# Connectors.net
KiCad netlist of a schematic drawn in Altium Designer
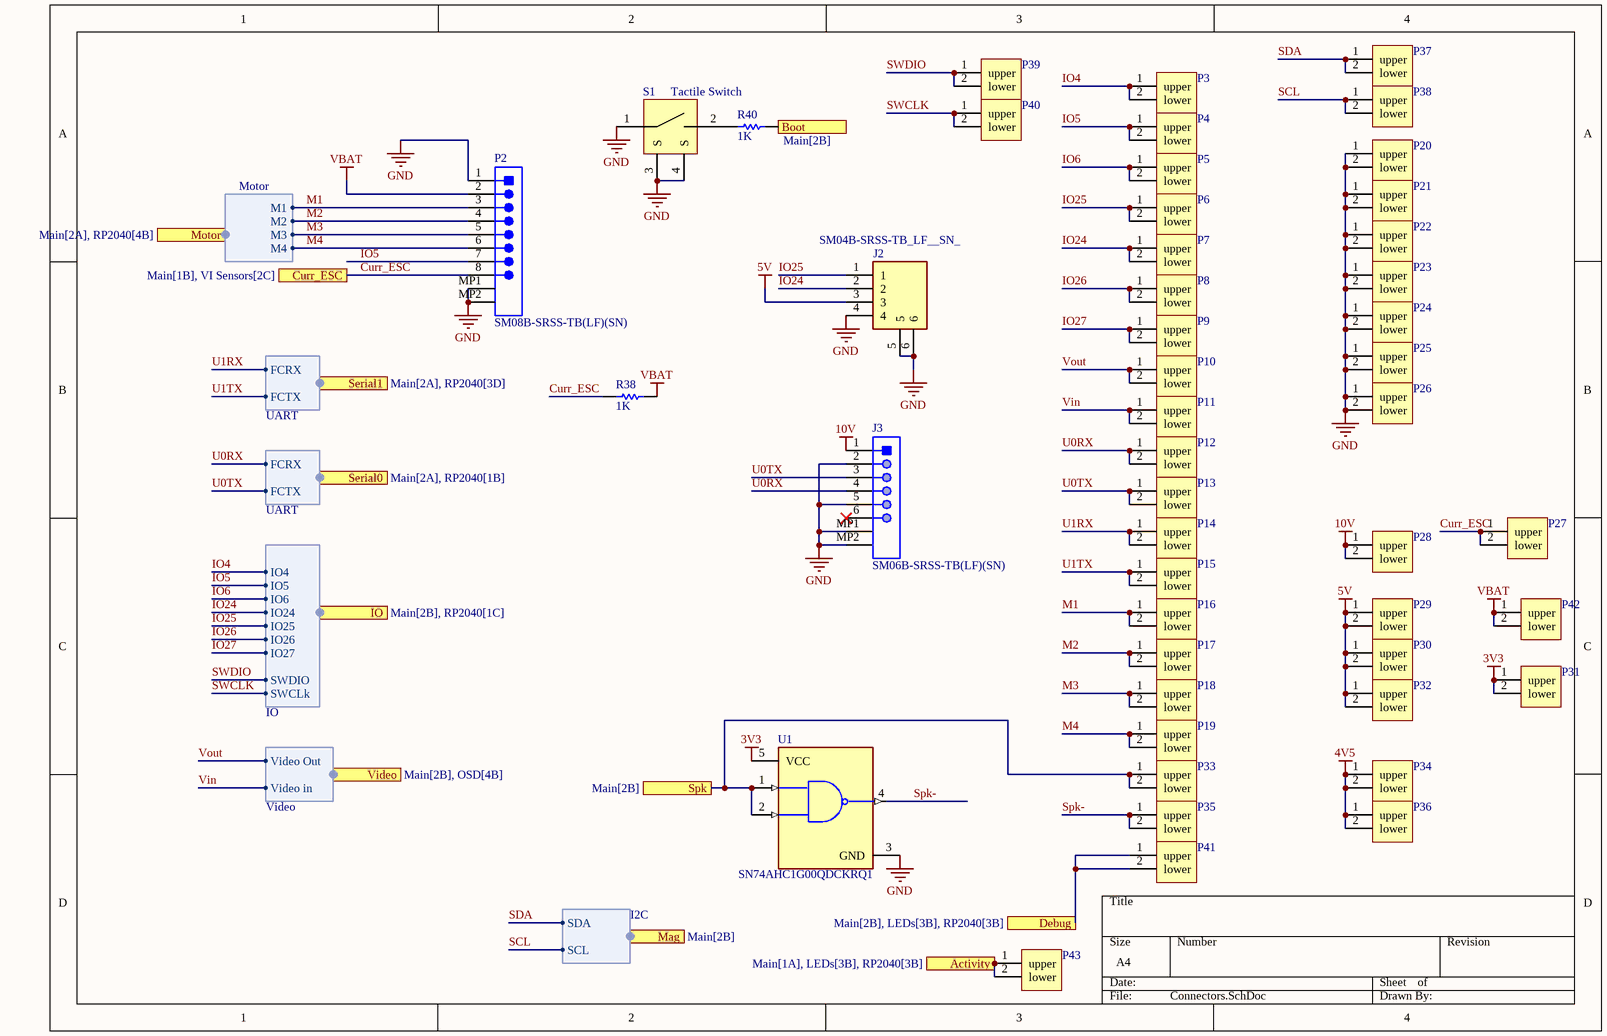
[diagram p0: Connectors.SchDoc]

(export (version "E")
  (design (tool "Eeschema 10.0.6"))
  (components
    (comp (ref "J2")
      (value "SM04B-SRSS-TB_LF__SN_")
      (footprint "SM04B-SRSS-TB(LFSN)")
      (description "Connector")
      (fields (field (name "MANUFACTURER_PART_NUMBER") "SM04B-SRSS-TB(LF)(SN)"))
      (libsource (lib "Custom Components") (part "SM04B-SRSS-TB_LF__SN_"))
    )
    (comp (ref "J3")
      (value "SM06B-SRSS-TB(LF)(SN)")
      (footprint "JST-SM06B-SRSS-TB_V")
      (description "Male Header, Pitch 1 mm, 1 x 6 Position, Height 2.95 mm, -25 to 85 degC, RoHS, Tape and Reel")
      (fields (field (name "MANUFACTURER") "JST"))
      (libsource (lib "Altium Content Vault") (part "CN-1P-2M-R6"))
    )
    (comp (ref "P2")
      (value "SM08B-SRSS-TB(LF)(SN)")
      (footprint "JST-SM08B-SRSS-TB_V")
      (description "Male Header, Pitch 1 mm, 1 x 8 Position, Height 2.95 mm, -25 to 85 degC, RoHS, Tape and Reel")
      (fields (field (name "MANUFACTURER") "JST"))
      (libsource (lib "Altium Content Vault") (part "CN-1P-2M-R8"))
    )
    (comp (ref "P3")
      (value "solder pad rounded double sided")
      (footprint "solder pad double sided rounded - duplicate")
      (libsource (lib "Custom Components") (part "solder pad rounded double sided"))
    )
    (comp (ref "P4")
      (value "solder pad rounded double sided")
      (footprint "solder pad double sided rounded - duplicate")
      (libsource (lib "Custom Components") (part "solder pad rounded double sided"))
    )
    (comp (ref "P5")
      (value "solder pad rounded double sided")
      (footprint "solder pad double sided rounded - duplicate")
      (libsource (lib "Custom Components") (part "solder pad rounded double sided"))
    )
    (comp (ref "P6")
      (value "solder pad rounded double sided")
      (footprint "solder pad double sided rounded - duplicate")
      (libsource (lib "Custom Components") (part "solder pad rounded double sided"))
    )
    (comp (ref "P7")
      (value "solder pad rounded double sided")
      (footprint "solder pad double sided rounded - duplicate")
      (libsource (lib "Custom Components") (part "solder pad rounded double sided"))
    )
    (comp (ref "P8")
      (value "solder pad rounded double sided")
      (footprint "solder pad double sided rounded - duplicate")
      (libsource (lib "Custom Components") (part "solder pad rounded double sided"))
    )
    (comp (ref "P9")
      (value "solder pad rounded double sided")
      (footprint "solder pad double sided rounded - duplicate")
      (libsource (lib "Custom Components") (part "solder pad rounded double sided"))
    )
    (comp (ref "P10")
      (value "solder pad rounded double sided")
      (footprint "solder pad double sided rounded - duplicate")
      (libsource (lib "Custom Components") (part "solder pad rounded double sided"))
    )
    (comp (ref "P11")
      (value "solder pad rounded double sided")
      (footprint "solder pad double sided rounded - duplicate")
      (libsource (lib "Custom Components") (part "solder pad rounded double sided"))
    )
    (comp (ref "P12")
      (value "solder pad rounded double sided")
      (footprint "solder pad double sided rounded - duplicate")
      (libsource (lib "Custom Components") (part "solder pad rounded double sided"))
    )
    (comp (ref "P13")
      (value "solder pad rounded double sided")
      (footprint "solder pad double sided rounded - duplicate")
      (libsource (lib "Custom Components") (part "solder pad rounded double sided"))
    )
    (comp (ref "P14")
      (value "solder pad rounded double sided")
      (footprint "solder pad double sided rounded - duplicate")
      (libsource (lib "Custom Components") (part "solder pad rounded double sided"))
    )
    (comp (ref "P15")
      (value "solder pad rounded double sided")
      (footprint "solder pad double sided rounded - duplicate")
      (libsource (lib "Custom Components") (part "solder pad rounded double sided"))
    )
    (comp (ref "P16")
      (value "solder pad rounded double sided")
      (footprint "solder pad double sided rounded - duplicate")
      (libsource (lib "Custom Components") (part "solder pad rounded double sided"))
    )
    (comp (ref "P17")
      (value "solder pad rounded double sided")
      (footprint "solder pad double sided rounded - duplicate")
      (libsource (lib "Custom Components") (part "solder pad rounded double sided"))
    )
    (comp (ref "P18")
      (value "solder pad rounded double sided")
      (footprint "solder pad double sided rounded - duplicate")
      (libsource (lib "Custom Components") (part "solder pad rounded double sided"))
    )
    (comp (ref "P19")
      (value "solder pad rounded double sided")
      (footprint "solder pad double sided rounded - duplicate")
      (libsource (lib "Custom Components") (part "solder pad rounded double sided"))
    )
    (comp (ref "P20")
      (value "solder pad square double sided")
      (footprint "solder pad double sided square")
      (libsource (lib "Custom Components") (part "solder pad square double sided"))
    )
    (comp (ref "P21")
      (value "solder pad square double sided")
      (footprint "solder pad double sided square")
      (libsource (lib "Custom Components") (part "solder pad square double sided"))
    )
    (comp (ref "P22")
      (value "solder pad square double sided")
      (footprint "solder pad double sided square")
      (libsource (lib "Custom Components") (part "solder pad square double sided"))
    )
    (comp (ref "P23")
      (value "solder pad square double sided")
      (footprint "solder pad double sided square")
      (libsource (lib "Custom Components") (part "solder pad square double sided"))
    )
    (comp (ref "P24")
      (value "solder pad square double sided")
      (footprint "solder pad double sided square")
      (libsource (lib "Custom Components") (part "solder pad square double sided"))
    )
    (comp (ref "P25")
      (value "solder pad square double sided")
      (footprint "solder pad double sided square")
      (libsource (lib "Custom Components") (part "solder pad square double sided"))
    )
    (comp (ref "P26")
      (value "solder pad square double sided")
      (footprint "solder pad double sided square")
      (libsource (lib "Custom Components") (part "solder pad square double sided"))
    )
    (comp (ref "P27")
      (value "solder pad rounded double sided")
      (footprint "solder pad double sided rounded - duplicate")
      (libsource (lib "Custom Components") (part "solder pad rounded double sided"))
    )
    (comp (ref "P28")
      (value "solder pad chamfered double sided")
      (footprint "solder pad double sided chamfered")
      (libsource (lib "Custom Components") (part "solder pad chamfered double sided"))
    )
    (comp (ref "P29")
      (value "solder pad chamfered double sided")
      (footprint "solder pad double sided chamfered")
      (libsource (lib "Custom Components") (part "solder pad chamfered double sided"))
    )
    (comp (ref "P30")
      (value "solder pad chamfered double sided")
      (footprint "solder pad double sided chamfered")
      (libsource (lib "Custom Components") (part "solder pad chamfered double sided"))
    )
    (comp (ref "P31")
      (value "solder pad chamfered double sided")
      (footprint "solder pad double sided chamfered")
      (libsource (lib "Custom Components") (part "solder pad chamfered double sided"))
    )
    (comp (ref "P32")
      (value "solder pad chamfered double sided")
      (footprint "solder pad double sided chamfered")
      (libsource (lib "Custom Components") (part "solder pad chamfered double sided"))
    )
    (comp (ref "P33")
      (value "solder pad rounded double sided")
      (footprint "solder pad double sided rounded - duplicate")
      (libsource (lib "Custom Components") (part "solder pad rounded double sided"))
    )
    (comp (ref "P34")
      (value "solder pad chamfered double sided")
      (footprint "solder pad double sided chamfered")
      (libsource (lib "Custom Components") (part "solder pad chamfered double sided"))
    )
    (comp (ref "P35")
      (value "solder pad rounded double sided")
      (footprint "solder pad double sided rounded - duplicate")
      (libsource (lib "Custom Components") (part "solder pad rounded double sided"))
    )
    (comp (ref "P36")
      (value "solder pad chamfered double sided")
      (footprint "solder pad double sided chamfered")
      (libsource (lib "Custom Components") (part "solder pad chamfered double sided"))
    )
    (comp (ref "P37")
      (value "solder pad rounded double sided")
      (footprint "solder pad double sided rounded - duplicate")
      (libsource (lib "Custom Components") (part "solder pad rounded double sided"))
    )
    (comp (ref "P38")
      (value "solder pad rounded double sided")
      (footprint "solder pad double sided rounded - duplicate")
      (libsource (lib "Custom Components") (part "solder pad rounded double sided"))
    )
    (comp (ref "P39")
      (value "solder pad rounded double sided")
      (footprint "solder pad double sided rounded - duplicate")
      (libsource (lib "Custom Components") (part "solder pad rounded double sided"))
    )
    (comp (ref "P40")
      (value "solder pad rounded double sided")
      (footprint "solder pad double sided rounded - duplicate")
      (libsource (lib "Custom Components") (part "solder pad rounded double sided"))
    )
    (comp (ref "P41")
      (value "solder pad rounded double sided")
      (footprint "solder pad double sided rounded - duplicate")
      (libsource (lib "Custom Components") (part "solder pad rounded double sided"))
    )
    (comp (ref "P42")
      (value "solder pad chamfered double sided")
      (footprint "solder pad double sided chamfered")
      (libsource (lib "Custom Components") (part "solder pad chamfered double sided"))
    )
    (comp (ref "P43")
      (value "solder pad rounded double sided")
      (footprint "solder pad double sided rounded - duplicate")
      (libsource (lib "Custom Components") (part "solder pad rounded double sided"))
    )
    (comp (ref "R38")
      (value "1K")
      (footprint "RESC0603(1608)_N")
      (description "Chipwiderstand, SMD, Baureihe MC, 1%")
      (fields (field (name "MANUFACTURER") "Multicomp"))
      (libsource (lib "Standardbauteile") (part "Res 1K"))
    )
    (comp (ref "R40")
      (value "1K")
      (footprint "RESC1005X40X25NL05T10")
      (fields (field (name "MANUFACTURER") "Yageo / Phycomp") (field (name "PART NUMBER") "RC0402JR-070RL"))
      (libsource (lib "Altium Content Vault") (part "RES"))
    )
    (comp (ref "S1")
      (value "Tactile Switch")
      (footprint "Tactile Switch")
      (libsource (lib "Custom Components") (part "Tactile Switch"))
    )
    (comp (ref "U1")
      (value "SN74AHC1G00QDCKRQ1")
      (footprint "FP-DCK0005A-IPC_A")
      (description "IC GATE NAND 1CH 2-INP SC70-5")
      (libsource (lib "Altium Content Vault") (part "4a1d673274a90161e31fa41c5f74738"))
    )
  )
  (nets
    (net (code "6") (name "/Activity") (class "Default")
      (node (ref "P43") (pin "1") (pinfunction "upper_1") (pintype "passive"))
      (node (ref "P43") (pin "2") (pinfunction "lower_2") (pintype "passive"))
    )
    (net (code "7") (name "/Boot") (class "Default")
      (node (ref "R40") (pin "2") (pinfunction "2_2") (pintype "passive"))
    )
    (net (code "8") (name "/Curr_ESC") (class "Default")
      (node (ref "P2") (pin "8") (pinfunction "8_8") (pintype "passive"))
      (node (ref "P27") (pin "1") (pinfunction "upper_1") (pintype "passive"))
      (node (ref "P27") (pin "2") (pinfunction "lower_2") (pintype "passive"))
      (node (ref "R38") (pin "1") (pinfunction "1_1") (pintype "passive"))
    )
    (net (code "9") (name "/Debug") (class "Default")
      (node (ref "P41") (pin "1") (pinfunction "upper_1") (pintype "passive"))
      (node (ref "P41") (pin "2") (pinfunction "lower_2") (pintype "passive"))
    )
    (net (code "10") (name "/IO4") (class "Default")
      (node (ref "P3") (pin "1") (pinfunction "upper_1") (pintype "passive"))
      (node (ref "P3") (pin "2") (pinfunction "lower_2") (pintype "passive"))
    )
    (net (code "11") (name "/IO5") (class "Default")
      (node (ref "P2") (pin "7") (pinfunction "7_7") (pintype "passive"))
      (node (ref "P4") (pin "1") (pinfunction "upper_1") (pintype "passive"))
      (node (ref "P4") (pin "2") (pinfunction "lower_2") (pintype "passive"))
    )
    (net (code "12") (name "/IO6") (class "Default")
      (node (ref "P5") (pin "1") (pinfunction "upper_1") (pintype "passive"))
      (node (ref "P5") (pin "2") (pinfunction "lower_2") (pintype "passive"))
    )
    (net (code "13") (name "/IO24") (class "Default")
      (node (ref "J2") (pin "2") (pinfunction "2_2") (pintype "passive"))
      (node (ref "P7") (pin "1") (pinfunction "upper_1") (pintype "passive"))
      (node (ref "P7") (pin "2") (pinfunction "lower_2") (pintype "passive"))
    )
    (net (code "14") (name "/IO25") (class "Default")
      (node (ref "J2") (pin "1") (pinfunction "1_1") (pintype "passive"))
      (node (ref "P6") (pin "1") (pinfunction "upper_1") (pintype "passive"))
      (node (ref "P6") (pin "2") (pinfunction "lower_2") (pintype "passive"))
    )
    (net (code "15") (name "/IO26") (class "Default")
      (node (ref "P8") (pin "1") (pinfunction "upper_1") (pintype "passive"))
      (node (ref "P8") (pin "2") (pinfunction "lower_2") (pintype "passive"))
    )
    (net (code "16") (name "/IO27") (class "Default")
      (node (ref "P9") (pin "1") (pinfunction "upper_1") (pintype "passive"))
      (node (ref "P9") (pin "2") (pinfunction "lower_2") (pintype "passive"))
    )
    (net (code "17") (name "/M1") (class "Default")
      (node (ref "P16") (pin "1") (pinfunction "upper_1") (pintype "passive"))
      (node (ref "P16") (pin "2") (pinfunction "lower_2") (pintype "passive"))
      (node (ref "P2") (pin "3") (pinfunction "3_3") (pintype "passive"))
    )
    (net (code "18") (name "/M2") (class "Default")
      (node (ref "P17") (pin "1") (pinfunction "upper_1") (pintype "passive"))
      (node (ref "P17") (pin "2") (pinfunction "lower_2") (pintype "passive"))
      (node (ref "P2") (pin "4") (pinfunction "4_4") (pintype "passive"))
    )
    (net (code "19") (name "/M3") (class "Default")
      (node (ref "P18") (pin "1") (pinfunction "upper_1") (pintype "passive"))
      (node (ref "P18") (pin "2") (pinfunction "lower_2") (pintype "passive"))
      (node (ref "P2") (pin "5") (pinfunction "5_5") (pintype "passive"))
    )
    (net (code "20") (name "/M4") (class "Default")
      (node (ref "P19") (pin "1") (pinfunction "upper_1") (pintype "passive"))
      (node (ref "P19") (pin "2") (pinfunction "lower_2") (pintype "passive"))
      (node (ref "P2") (pin "6") (pinfunction "6_6") (pintype "passive"))
    )
    (net (code "21") (name "/SCL") (class "Default")
      (node (ref "P38") (pin "1") (pinfunction "upper_1") (pintype "passive"))
      (node (ref "P38") (pin "2") (pinfunction "lower_2") (pintype "passive"))
    )
    (net (code "22") (name "/SDA") (class "Default")
      (node (ref "P37") (pin "1") (pinfunction "upper_1") (pintype "passive"))
      (node (ref "P37") (pin "2") (pinfunction "lower_2") (pintype "passive"))
    )
    (net (code "23") (name "/SWCLK") (class "Default")
      (node (ref "P40") (pin "1") (pinfunction "upper_1") (pintype "passive"))
      (node (ref "P40") (pin "2") (pinfunction "lower_2") (pintype "passive"))
    )
    (net (code "24") (name "/SWDIO") (class "Default")
      (node (ref "P39") (pin "1") (pinfunction "upper_1") (pintype "passive"))
      (node (ref "P39") (pin "2") (pinfunction "lower_2") (pintype "passive"))
    )
    (net (code "25") (name "/Spk") (class "Default")
      (node (ref "P33") (pin "1") (pinfunction "upper_1") (pintype "passive"))
      (node (ref "P33") (pin "2") (pinfunction "lower_2") (pintype "passive"))
      (node (ref "U1") (pin "1") (pinfunction "A_1") (pintype "input"))
      (node (ref "U1") (pin "2") (pinfunction "B_2") (pintype "input"))
    )
    (net (code "26") (name "/Spk-") (class "Default")
      (node (ref "P35") (pin "1") (pinfunction "upper_1") (pintype "passive"))
      (node (ref "P35") (pin "2") (pinfunction "lower_2") (pintype "passive"))
      (node (ref "U1") (pin "4") (pinfunction "Y_4") (pintype "output"))
    )
    (net (code "27") (name "/U0RX") (class "Default")
      (node (ref "J3") (pin "4") (pinfunction "4_4") (pintype "passive"))
      (node (ref "P12") (pin "1") (pinfunction "upper_1") (pintype "passive"))
      (node (ref "P12") (pin "2") (pinfunction "lower_2") (pintype "passive"))
    )
    (net (code "28") (name "/U0TX") (class "Default")
      (node (ref "J3") (pin "3") (pinfunction "3_3") (pintype "passive"))
      (node (ref "P13") (pin "1") (pinfunction "upper_1") (pintype "passive"))
      (node (ref "P13") (pin "2") (pinfunction "lower_2") (pintype "passive"))
    )
    (net (code "29") (name "/U1RX") (class "Default")
      (node (ref "P14") (pin "1") (pinfunction "upper_1") (pintype "passive"))
      (node (ref "P14") (pin "2") (pinfunction "lower_2") (pintype "passive"))
    )
    (net (code "30") (name "/U1TX") (class "Default")
      (node (ref "P15") (pin "1") (pinfunction "upper_1") (pintype "passive"))
      (node (ref "P15") (pin "2") (pinfunction "lower_2") (pintype "passive"))
    )
    (net (code "31") (name "/Vin") (class "Default")
      (node (ref "P11") (pin "1") (pinfunction "upper_1") (pintype "passive"))
      (node (ref "P11") (pin "2") (pinfunction "lower_2") (pintype "passive"))
    )
    (net (code "32") (name "/Vout") (class "Default")
      (node (ref "P10") (pin "1") (pinfunction "upper_1") (pintype "passive"))
      (node (ref "P10") (pin "2") (pinfunction "lower_2") (pintype "passive"))
    )
    (net (code "38") (name "3V3") (class "Default")
      (node (ref "P31") (pin "1") (pinfunction "upper_1") (pintype "passive"))
      (node (ref "P31") (pin "2") (pinfunction "lower_2") (pintype "passive"))
      (node (ref "U1") (pin "5") (pinfunction "VCC_5") (pintype "power_in"))
    )
    (net (code "39") (name "4V5") (class "Default")
      (node (ref "P34") (pin "1") (pinfunction "upper_1") (pintype "passive"))
      (node (ref "P34") (pin "2") (pinfunction "lower_2") (pintype "passive"))
      (node (ref "P36") (pin "1") (pinfunction "upper_1") (pintype "passive"))
      (node (ref "P36") (pin "2") (pinfunction "lower_2") (pintype "passive"))
    )
    (net (code "40") (name "5V") (class "Default")
      (node (ref "J2") (pin "3") (pinfunction "3_3") (pintype "passive"))
      (node (ref "P29") (pin "1") (pinfunction "upper_1") (pintype "passive"))
      (node (ref "P29") (pin "2") (pinfunction "lower_2") (pintype "passive"))
      (node (ref "P30") (pin "1") (pinfunction "upper_1") (pintype "passive"))
      (node (ref "P30") (pin "2") (pinfunction "lower_2") (pintype "passive"))
      (node (ref "P32") (pin "1") (pinfunction "upper_1") (pintype "passive"))
      (node (ref "P32") (pin "2") (pinfunction "lower_2") (pintype "passive"))
    )
    (net (code "41") (name "10V") (class "Default")
      (node (ref "J3") (pin "1") (pinfunction "1_1") (pintype "passive"))
      (node (ref "P28") (pin "1") (pinfunction "upper_1") (pintype "passive"))
      (node (ref "P28") (pin "2") (pinfunction "lower_2") (pintype "passive"))
    )
    (net (code "42") (name "GND") (class "Default")
      (node (ref "J2") (pin "4") (pinfunction "4_4") (pintype "passive"))
      (node (ref "J2") (pin "5") (pinfunction "5_5") (pintype "passive"))
      (node (ref "J2") (pin "6") (pinfunction "6_6") (pintype "passive"))
      (node (ref "J3") (pin "2") (pinfunction "2_2") (pintype "passive"))
      (node (ref "J3") (pin "5") (pinfunction "5_5") (pintype "passive"))
      (node (ref "J3") (pin "MP1") (pinfunction "MP1_MP1") (pintype "passive"))
      (node (ref "J3") (pin "MP2") (pinfunction "MP2_MP2") (pintype "passive"))
      (node (ref "P2") (pin "1") (pinfunction "1_1") (pintype "passive"))
      (node (ref "P2") (pin "MP1") (pinfunction "MP1_MP1") (pintype "passive"))
      (node (ref "P2") (pin "MP2") (pinfunction "MP2_MP2") (pintype "passive"))
      (node (ref "P20") (pin "1") (pinfunction "upper_1") (pintype "passive"))
      (node (ref "P20") (pin "2") (pinfunction "lower_2") (pintype "passive"))
      (node (ref "P21") (pin "1") (pinfunction "upper_1") (pintype "passive"))
      (node (ref "P21") (pin "2") (pinfunction "lower_2") (pintype "passive"))
      (node (ref "P22") (pin "1") (pinfunction "upper_1") (pintype "passive"))
      (node (ref "P22") (pin "2") (pinfunction "lower_2") (pintype "passive"))
      (node (ref "P23") (pin "1") (pinfunction "upper_1") (pintype "passive"))
      (node (ref "P23") (pin "2") (pinfunction "lower_2") (pintype "passive"))
      (node (ref "P24") (pin "1") (pinfunction "upper_1") (pintype "passive"))
      (node (ref "P24") (pin "2") (pinfunction "lower_2") (pintype "passive"))
      (node (ref "P25") (pin "1") (pinfunction "upper_1") (pintype "passive"))
      (node (ref "P25") (pin "2") (pinfunction "lower_2") (pintype "passive"))
      (node (ref "P26") (pin "1") (pinfunction "upper_1") (pintype "passive"))
      (node (ref "P26") (pin "2") (pinfunction "lower_2") (pintype "passive"))
      (node (ref "S1") (pin "1") (pintype "passive"))
      (node (ref "S1") (pin "3") (pinfunction "S_3") (pintype "passive"))
      (node (ref "S1") (pin "4") (pinfunction "S_4") (pintype "passive"))
      (node (ref "U1") (pin "3") (pinfunction "GND_3") (pintype "power_in"))
    )
    (net (code "43") (name "Net-(R40-Pad1)") (class "Default")
      (node (ref "R40") (pin "1") (pinfunction "1_1") (pintype "passive"))
      (node (ref "S1") (pin "2") (pintype "passive"))
    )
    (net (code "44") (name "VBAT") (class "Default")
      (node (ref "P2") (pin "2") (pinfunction "2_2") (pintype "passive"))
      (node (ref "P42") (pin "1") (pinfunction "upper_1") (pintype "passive"))
      (node (ref "P42") (pin "2") (pinfunction "lower_2") (pintype "passive"))
      (node (ref "R38") (pin "2") (pinfunction "2_2") (pintype "passive"))
    )
    (net (code "45") (name "unconnected-(J3-Pad6)") (class "Default")
      (node (ref "J3") (pin "6") (pinfunction "6_6") (pintype "passive+no_connect"))
    )
  )
)
